# RFBoardSchematics.net
KiCad netlist of a schematic drawn in EAGLE
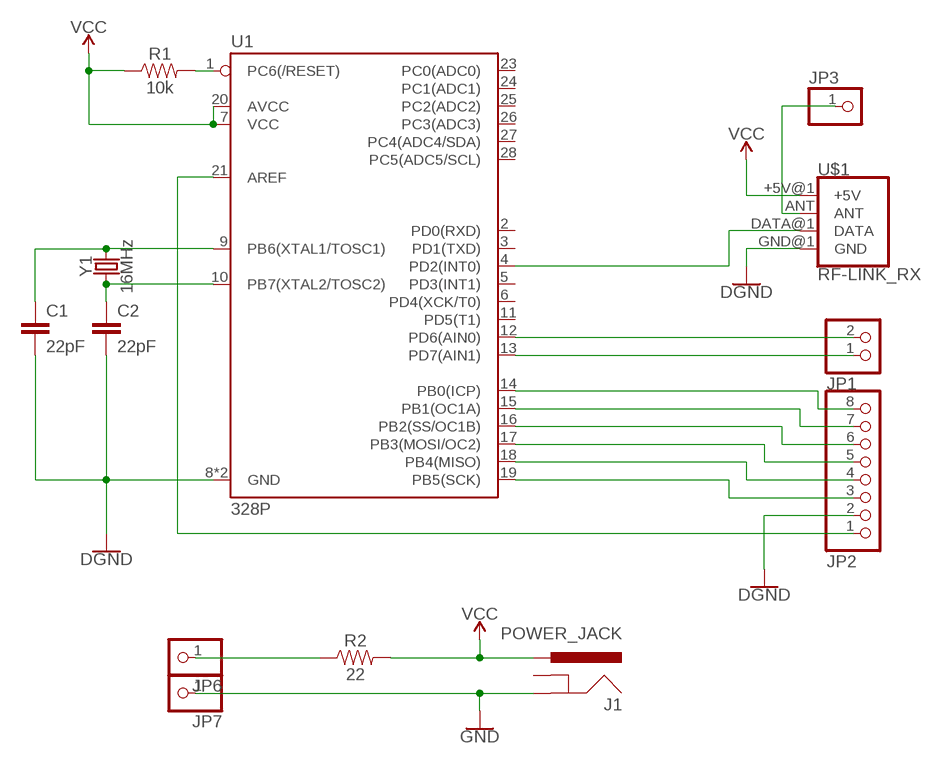
[diagram p0: schematic, sheet 1]

(export (version "E")
  (design (tool "Eeschema 10.0.6"))
  (components
    (comp (ref "C1")
      (value "22pF")
      (footprint "eagle-import:CAP-PTH-2.54")
      (libsource (lib "eagle-import") (part "22PF-PTH-2.54MM-200V-5%"))
    )
    (comp (ref "C2")
      (value "22pF")
      (footprint "eagle-import:CAP-PTH-2.54")
      (libsource (lib "eagle-import") (part "22PF-PTH-2.54MM-200V-5%"))
    )
    (comp (ref "J1")
      (value "POWER_JACK")
      (footprint "eagle-import:POWER_JACK_PTH")
      (libsource (lib "eagle-import") (part "POWER_JACK"))
    )
    (comp (ref "JP1")
      (value "PINHD-1X2")
      (footprint "eagle-import:1X02")
      (libsource (lib "eagle-import") (part "PINHD-1X2"))
    )
    (comp (ref "JP2")
      (value "PINHD-1X8")
      (footprint "eagle-import:1X08")
      (libsource (lib "eagle-import") (part "PINHD-1X8"))
    )
    (comp (ref "JP3")
      (value "PINHD-1X1")
      (footprint "eagle-import:1X01")
      (libsource (lib "eagle-import") (part "PINHD-1X1"))
    )
    (comp (ref "JP6")
      (value "PINHD-1X1")
      (footprint "eagle-import:1X01")
      (libsource (lib "eagle-import") (part "PINHD-1X1"))
    )
    (comp (ref "JP7")
      (value "PINHD-1X1")
      (footprint "eagle-import:1X01")
      (libsource (lib "eagle-import") (part "PINHD-1X1"))
    )
    (comp (ref "R1")
      (value "10k")
      (footprint "eagle-import:AXIAL-0.3")
      (libsource (lib "eagle-import") (part "10KOHM-HORIZ-1/4W-1%"))
    )
    (comp (ref "R2")
      (value "22")
      (footprint "eagle-import:AXIAL-0.3")
      (libsource (lib "eagle-import") (part "10OHM-HORIZ-1/4W-1%"))
    )
    (comp (ref "U$1")
      (value "RF-LINK_RX")
      (footprint "eagle-import:RF-LINK_RX")
      (libsource (lib "eagle-import") (part "RF-LINK_RX"))
    )
    (comp (ref "U1")
      (value "328P")
      (footprint "eagle-import:DIP28")
      (libsource (lib "eagle-import") (part "ATMEGA328P_PDIP"))
    )
    (comp (ref "Y1")
      (value "16MHz")
      (footprint "eagle-import:HC49US")
      (libsource (lib "eagle-import") (part "CRYSTAL-16MHZPTH-HC49US"))
    )
  )
  (nets
    (net (code "1") (name "DGND") (class "Default")
      (node (ref "C1") (pin "2") (pinfunction "2_2") (pintype "passive"))
      (node (ref "C2") (pin "2") (pinfunction "2_2") (pintype "passive"))
      (node (ref "J1") (pin "GND") (pinfunction "GND_GND") (pintype "bidirectional"))
      (node (ref "JP2") (pin "2") (pinfunction "2_2") (pintype "passive"))
      (node (ref "JP7") (pin "1") (pinfunction "1_1") (pintype "passive"))
      (node (ref "U$1") (pin "GND@1") (pinfunction "GND_GND@1") (pintype "power_in"))
      (node (ref "U1") (pin "22") (pinfunction "GND_22") (pintype "bidirectional"))
      (node (ref "U1") (pin "8") (pinfunction "GND_8") (pintype "bidirectional"))
    )
    (net (code "2") (name "Net-(JP3-Pad1)") (class "Default")
      (node (ref "JP3") (pin "1") (pinfunction "1_1") (pintype "passive"))
      (node (ref "U$1") (pin "ANT") (pinfunction "ANT_ANT") (pintype "passive"))
    )
    (net (code "3") (name "Net-(R1-2)") (class "Default")
      (node (ref "R1") (pin "P$2") (pinfunction "2_P$2") (pintype "passive"))
      (node (ref "U1") (pin "1") (pinfunction "PC6(/RESET)_1") (pintype "bidirectional"))
    )
    (net (code "4") (name "Net-(R2-1)") (class "Default")
      (node (ref "JP6") (pin "1") (pinfunction "1_1") (pintype "passive"))
      (node (ref "R2") (pin "P$1") (pinfunction "1_P$1") (pintype "passive"))
    )
    (net (code "5") (name "Net-(U$1-DATA)") (class "Default")
      (node (ref "U$1") (pin "DATA@1") (pinfunction "DATA_DATA@1") (pintype "input"))
      (node (ref "U1") (pin "4") (pinfunction "PD2(INT0)_4") (pintype "bidirectional"))
    )
    (net (code "6") (name "Net-(U1-AREF)") (class "Default")
      (node (ref "JP2") (pin "1") (pinfunction "1_1") (pintype "passive"))
      (node (ref "U1") (pin "21") (pinfunction "AREF_21") (pintype "bidirectional"))
    )
    (net (code "7") (name "Net-(U1-PB0(ICP))") (class "Default")
      (node (ref "JP2") (pin "8") (pinfunction "8_8") (pintype "passive"))
      (node (ref "U1") (pin "14") (pinfunction "PB0(ICP)_14") (pintype "bidirectional"))
    )
    (net (code "8") (name "Net-(U1-PB1(OC1A))") (class "Default")
      (node (ref "JP2") (pin "7") (pinfunction "7_7") (pintype "passive"))
      (node (ref "U1") (pin "15") (pinfunction "PB1(OC1A)_15") (pintype "bidirectional"))
    )
    (net (code "9") (name "Net-(U1-PB2(SS{slash}OC1B))") (class "Default")
      (node (ref "JP2") (pin "6") (pinfunction "6_6") (pintype "passive"))
      (node (ref "U1") (pin "16") (pinfunction "PB2(SS/OC1B)_16") (pintype "bidirectional"))
    )
    (net (code "10") (name "Net-(U1-PB3(MOSI{slash}OC2))") (class "Default")
      (node (ref "JP2") (pin "5") (pinfunction "5_5") (pintype "passive"))
      (node (ref "U1") (pin "17") (pinfunction "PB3(MOSI/OC2)_17") (pintype "bidirectional"))
    )
    (net (code "11") (name "Net-(U1-PB4(MISO))") (class "Default")
      (node (ref "JP2") (pin "4") (pinfunction "4_4") (pintype "passive"))
      (node (ref "U1") (pin "18") (pinfunction "PB4(MISO)_18") (pintype "bidirectional"))
    )
    (net (code "12") (name "Net-(U1-PB5(SCK))") (class "Default")
      (node (ref "JP2") (pin "3") (pinfunction "3_3") (pintype "passive"))
      (node (ref "U1") (pin "19") (pinfunction "PB5(SCK)_19") (pintype "bidirectional"))
    )
    (net (code "13") (name "Net-(U1-PB6(XTAL1{slash}TOSC1))") (class "Default")
      (node (ref "C1") (pin "1") (pinfunction "1_1") (pintype "passive"))
      (node (ref "U1") (pin "9") (pinfunction "PB6(XTAL1/TOSC1)_9") (pintype "bidirectional"))
      (node (ref "Y1") (pin "2") (pinfunction "2_2") (pintype "passive"))
    )
    (net (code "14") (name "Net-(U1-PB7(XTAL2{slash}TOSC2))") (class "Default")
      (node (ref "C2") (pin "1") (pinfunction "1_1") (pintype "passive"))
      (node (ref "U1") (pin "10") (pinfunction "PB7(XTAL2/TOSC2)_10") (pintype "bidirectional"))
      (node (ref "Y1") (pin "1") (pinfunction "1_1") (pintype "passive"))
    )
    (net (code "15") (name "Net-(U1-PD6(AIN0))") (class "Default")
      (node (ref "JP1") (pin "2") (pinfunction "2_2") (pintype "passive"))
      (node (ref "U1") (pin "12") (pinfunction "PD6(AIN0)_12") (pintype "bidirectional"))
    )
    (net (code "16") (name "Net-(U1-PD7(AIN1))") (class "Default")
      (node (ref "JP1") (pin "1") (pinfunction "1_1") (pintype "passive"))
      (node (ref "U1") (pin "13") (pinfunction "PD7(AIN1)_13") (pintype "bidirectional"))
    )
    (net (code "17") (name "VCC") (class "Default")
      (node (ref "J1") (pin "PWR") (pinfunction "PWR_PWR") (pintype "bidirectional"))
      (node (ref "R1") (pin "P$1") (pinfunction "1_P$1") (pintype "passive"))
      (node (ref "R2") (pin "P$2") (pinfunction "2_P$2") (pintype "passive"))
      (node (ref "U$1") (pin "+5V@1") (pinfunction "+5V_+5V@1") (pintype "power_in"))
      (node (ref "U1") (pin "20") (pinfunction "AVCC_20") (pintype "bidirectional"))
      (node (ref "U1") (pin "7") (pinfunction "VCC_7") (pintype "bidirectional"))
    )
    (net (code "18") (name "unconnected-(J1-PadGNDBREAK)") (class "Default")
      (node (ref "J1") (pin "GNDBREAK") (pinfunction "GNDBREAK_GNDBREAK") (pintype "bidirectional"))
    )
    (net (code "19") (name "unconnected-(U1-PC0(ADC0)-Pad23)") (class "Default")
      (node (ref "U1") (pin "23") (pinfunction "PC0(ADC0)_23") (pintype "bidirectional"))
    )
    (net (code "20") (name "unconnected-(U1-PC1(ADC1)-Pad24)") (class "Default")
      (node (ref "U1") (pin "24") (pinfunction "PC1(ADC1)_24") (pintype "bidirectional"))
    )
    (net (code "21") (name "unconnected-(U1-PC2(ADC2)-Pad25)") (class "Default")
      (node (ref "U1") (pin "25") (pinfunction "PC2(ADC2)_25") (pintype "bidirectional"))
    )
    (net (code "22") (name "unconnected-(U1-PC3(ADC3)-Pad26)") (class "Default")
      (node (ref "U1") (pin "26") (pinfunction "PC3(ADC3)_26") (pintype "bidirectional"))
    )
    (net (code "23") (name "unconnected-(U1-PC4(ADC4{slash}SDA)-Pad27)") (class "Default")
      (node (ref "U1") (pin "27") (pinfunction "PC4(ADC4/SDA)_27") (pintype "bidirectional"))
    )
    (net (code "24") (name "unconnected-(U1-PC5(ADC5{slash}SCL)-Pad28)") (class "Default")
      (node (ref "U1") (pin "28") (pinfunction "PC5(ADC5/SCL)_28") (pintype "bidirectional"))
    )
    (net (code "25") (name "unconnected-(U1-PD0(RXD)-Pad2)") (class "Default")
      (node (ref "U1") (pin "2") (pinfunction "PD0(RXD)_2") (pintype "bidirectional"))
    )
    (net (code "26") (name "unconnected-(U1-PD1(TXD)-Pad3)") (class "Default")
      (node (ref "U1") (pin "3") (pinfunction "PD1(TXD)_3") (pintype "bidirectional"))
    )
    (net (code "27") (name "unconnected-(U1-PD3(INT1)-Pad5)") (class "Default")
      (node (ref "U1") (pin "5") (pinfunction "PD3(INT1)_5") (pintype "bidirectional"))
    )
    (net (code "28") (name "unconnected-(U1-PD4(XCK{slash}T0)-Pad6)") (class "Default")
      (node (ref "U1") (pin "6") (pinfunction "PD4(XCK/T0)_6") (pintype "bidirectional"))
    )
    (net (code "29") (name "unconnected-(U1-PD5(T1)-Pad11)") (class "Default")
      (node (ref "U1") (pin "11") (pinfunction "PD5(T1)_11") (pintype "bidirectional"))
    )
  )
)
